# EXT1.net
KiCad netlist of a schematic drawn in EAGLE
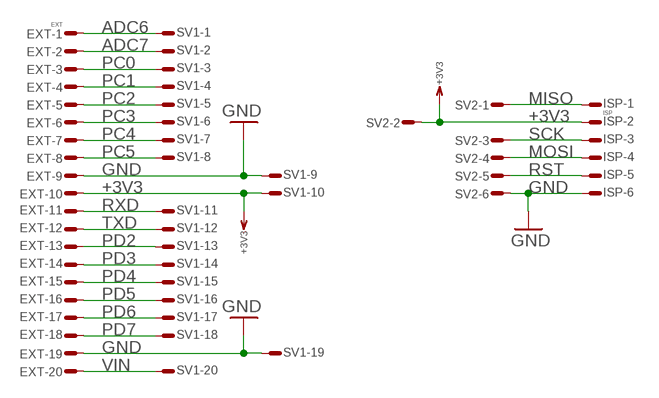
[diagram p0: schematic, sheet 1]

(export (version "E")
  (design (tool "Eeschema 10.0.6"))
  (components
    (comp (ref "EXT")
      (value "EXT")
      (footprint "eagle-import:ML20S")
      (libsource (lib "eagle-import") (part "ML20?ES"))
    )
    (comp (ref "ISP")
      (value "ISP")
      (footprint "eagle-import:ML6S")
      (libsource (lib "eagle-import") (part "ML6ES"))
    )
    (comp (ref "SV1")
      (value "ML20LE")
      (footprint "eagle-import:ML20L")
      (libsource (lib "eagle-import") (part "ML20?EL"))
    )
    (comp (ref "SV2")
      (value "ML6EM")
      (footprint "eagle-import:ML6")
      (libsource (lib "eagle-import") (part "ML6EM"))
    )
  )
  (nets
    (net (code "1") (name "+3V3") (class "Default")
      (node (ref "EXT") (pin "10") (pinfunction "S_10") (pintype "passive"))
      (node (ref "ISP") (pin "2") (pinfunction "S_2") (pintype "passive"))
      (node (ref "SV1") (pin "10") (pinfunction "S_10") (pintype "passive"))
      (node (ref "SV2") (pin "2") (pinfunction "S_2") (pintype "passive"))
    )
    (net (code "2") (name "/ADC6") (class "Default")
      (node (ref "EXT") (pin "1") (pinfunction "S_1") (pintype "passive"))
      (node (ref "SV1") (pin "1") (pinfunction "S_1") (pintype "passive"))
    )
    (net (code "3") (name "/ADC7") (class "Default")
      (node (ref "EXT") (pin "2") (pinfunction "S_2") (pintype "passive"))
      (node (ref "SV1") (pin "2") (pinfunction "S_2") (pintype "passive"))
    )
    (net (code "4") (name "/MISO") (class "Default")
      (node (ref "ISP") (pin "1") (pinfunction "S_1") (pintype "passive"))
      (node (ref "SV2") (pin "1") (pinfunction "S_1") (pintype "passive"))
    )
    (net (code "5") (name "/MOSI") (class "Default")
      (node (ref "ISP") (pin "4") (pinfunction "S_4") (pintype "passive"))
      (node (ref "SV2") (pin "4") (pinfunction "S_4") (pintype "passive"))
    )
    (net (code "6") (name "/PC0") (class "Default")
      (node (ref "EXT") (pin "3") (pinfunction "S_3") (pintype "passive"))
      (node (ref "SV1") (pin "3") (pinfunction "S_3") (pintype "passive"))
    )
    (net (code "7") (name "/PC1") (class "Default")
      (node (ref "EXT") (pin "4") (pinfunction "S_4") (pintype "passive"))
      (node (ref "SV1") (pin "4") (pinfunction "S_4") (pintype "passive"))
    )
    (net (code "8") (name "/PC2") (class "Default")
      (node (ref "EXT") (pin "5") (pinfunction "S_5") (pintype "passive"))
      (node (ref "SV1") (pin "5") (pinfunction "S_5") (pintype "passive"))
    )
    (net (code "9") (name "/PC3") (class "Default")
      (node (ref "EXT") (pin "6") (pinfunction "S_6") (pintype "passive"))
      (node (ref "SV1") (pin "6") (pinfunction "S_6") (pintype "passive"))
    )
    (net (code "10") (name "/PC4") (class "Default")
      (node (ref "EXT") (pin "7") (pinfunction "S_7") (pintype "passive"))
      (node (ref "SV1") (pin "7") (pinfunction "S_7") (pintype "passive"))
    )
    (net (code "11") (name "/PC5") (class "Default")
      (node (ref "EXT") (pin "8") (pinfunction "S_8") (pintype "passive"))
      (node (ref "SV1") (pin "8") (pinfunction "S_8") (pintype "passive"))
    )
    (net (code "12") (name "/PD2") (class "Default")
      (node (ref "EXT") (pin "13") (pinfunction "S_13") (pintype "passive"))
      (node (ref "SV1") (pin "13") (pinfunction "S_13") (pintype "passive"))
    )
    (net (code "13") (name "/PD3") (class "Default")
      (node (ref "EXT") (pin "14") (pinfunction "S_14") (pintype "passive"))
      (node (ref "SV1") (pin "14") (pinfunction "S_14") (pintype "passive"))
    )
    (net (code "14") (name "/PD4") (class "Default")
      (node (ref "EXT") (pin "15") (pinfunction "S_15") (pintype "passive"))
      (node (ref "SV1") (pin "15") (pinfunction "S_15") (pintype "passive"))
    )
    (net (code "15") (name "/PD5") (class "Default")
      (node (ref "EXT") (pin "16") (pinfunction "S_16") (pintype "passive"))
      (node (ref "SV1") (pin "16") (pinfunction "S_16") (pintype "passive"))
    )
    (net (code "16") (name "/PD6") (class "Default")
      (node (ref "EXT") (pin "17") (pinfunction "S_17") (pintype "passive"))
      (node (ref "SV1") (pin "17") (pinfunction "S_17") (pintype "passive"))
    )
    (net (code "17") (name "/PD7") (class "Default")
      (node (ref "EXT") (pin "18") (pinfunction "S_18") (pintype "passive"))
      (node (ref "SV1") (pin "18") (pinfunction "S_18") (pintype "passive"))
    )
    (net (code "18") (name "/RST") (class "Default")
      (node (ref "ISP") (pin "5") (pinfunction "S_5") (pintype "passive"))
      (node (ref "SV2") (pin "5") (pinfunction "S_5") (pintype "passive"))
    )
    (net (code "19") (name "/RXD") (class "Default")
      (node (ref "EXT") (pin "11") (pinfunction "S_11") (pintype "passive"))
      (node (ref "SV1") (pin "11") (pinfunction "S_11") (pintype "passive"))
    )
    (net (code "20") (name "/SCK") (class "Default")
      (node (ref "ISP") (pin "3") (pinfunction "S_3") (pintype "passive"))
      (node (ref "SV2") (pin "3") (pinfunction "S_3") (pintype "passive"))
    )
    (net (code "21") (name "/TXD") (class "Default")
      (node (ref "EXT") (pin "12") (pinfunction "S_12") (pintype "passive"))
      (node (ref "SV1") (pin "12") (pinfunction "S_12") (pintype "passive"))
    )
    (net (code "22") (name "/VIN") (class "Default")
      (node (ref "EXT") (pin "20") (pinfunction "S_20") (pintype "passive"))
      (node (ref "SV1") (pin "20") (pinfunction "S_20") (pintype "passive"))
    )
    (net (code "23") (name "GND") (class "Default")
      (node (ref "EXT") (pin "19") (pinfunction "S_19") (pintype "passive"))
      (node (ref "EXT") (pin "9") (pinfunction "S_9") (pintype "passive"))
      (node (ref "ISP") (pin "6") (pinfunction "S_6") (pintype "passive"))
      (node (ref "SV1") (pin "19") (pinfunction "S_19") (pintype "passive"))
      (node (ref "SV1") (pin "9") (pinfunction "S_9") (pintype "passive"))
      (node (ref "SV2") (pin "6") (pinfunction "S_6") (pintype "passive"))
    )
  )
)
